# LCD_PCB_SCHEMETIC.net
KiCad netlist of a schematic drawn in Altium Designer
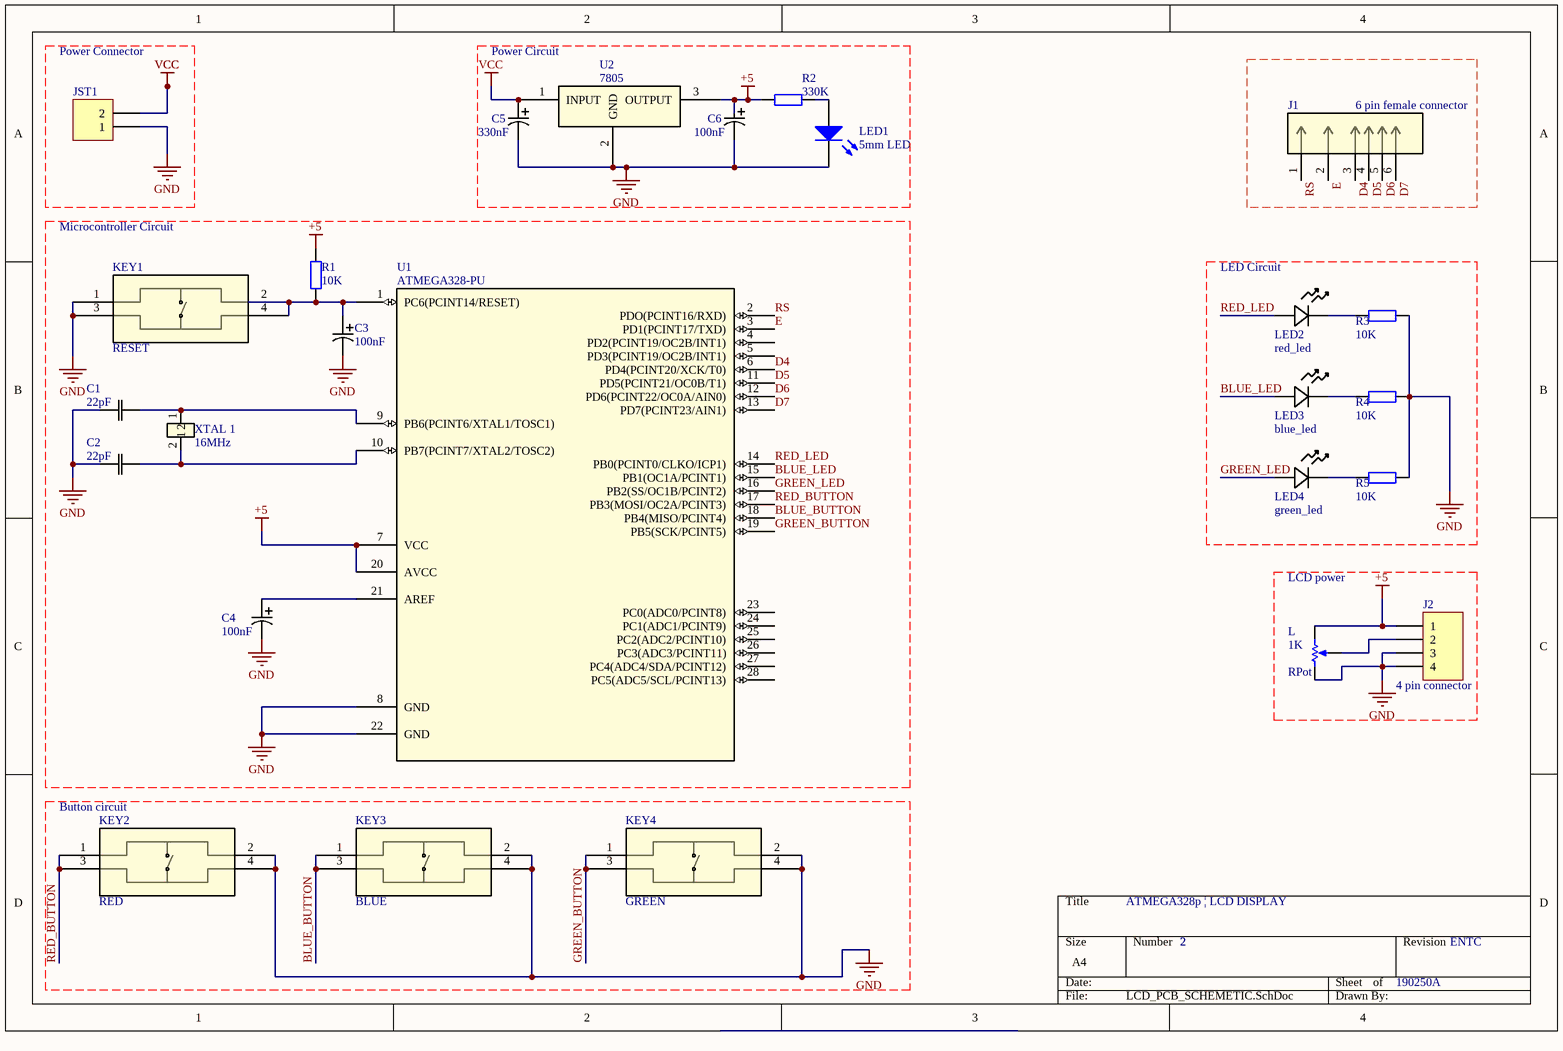
[diagram p0: LCD_PCB_SCHEMETIC.SchDoc]

(export (version "E")
  (design (tool "Eeschema 10.0.6"))
  (components
    (comp (ref "C1")
      (value "22pF")
      (footprint "CAP_K220J15C0GF53L2_VIS")
      (description "No Description Available")
      (fields
        (field (name "MANUFACTURER_PART_NUMBER") "K220J15C0GF53L2")
        (field (name "COPYRIGHT") "Copyright (C) 2018 Accelerated Designs. All rights reserved")
      )
      (libsource (lib "2021-05-23_06-09-59") (part "K220J15C0GF53L2"))
    )
    (comp (ref "C2")
      (value "22pF")
      (footprint "CAP_K220J15C0GF53L2_VIS")
      (description "No Description Available")
      (fields
        (field (name "MANUFACTURER_PART_NUMBER") "K220J15C0GF53L2")
        (field (name "COPYRIGHT") "Copyright (C) 2018 Accelerated Designs. All rights reserved")
      )
      (libsource (lib "2021-05-23_06-09-59") (part "K220J15C0GF53L2"))
    )
    (comp (ref "C3")
      (value "100nF")
      (footprint "PCAP_10x16_PAN")
      (description "No Description Available")
      (fields
        (field (name "MANUFACTURER_PART_NUMBER") "ECA2GM4R7")
        (field (name "COPYRIGHT") "Copyright (C) 2018 Accelerated Designs. All rights reserved")
      )
      (libsource (lib "2021-05-23_06-26-49") (part "ECA2GM4R7"))
    )
    (comp (ref "C4")
      (value "100nF")
      (footprint "PCAP_10x16_PAN")
      (description "No Description Available")
      (fields
        (field (name "MANUFACTURER_PART_NUMBER") "ECA2GM4R7")
        (field (name "COPYRIGHT") "Copyright (C) 2018 Accelerated Designs. All rights reserved")
      )
      (libsource (lib "2021-05-23_06-26-49") (part "ECA2GM4R7"))
    )
    (comp (ref "C5")
      (value "330nF")
      (footprint "PCAP_10x16_PAN")
      (description "No Description Available")
      (fields
        (field (name "MANUFACTURER_PART_NUMBER") "ECA2GM4R7")
        (field (name "COPYRIGHT") "Copyright (C) 2018 Accelerated Designs. All rights reserved")
      )
      (libsource (lib "2021-05-23_06-26-49") (part "ECA2GM4R7"))
    )
    (comp (ref "C6")
      (value "100nF")
      (footprint "PCAP_10x16_PAN")
      (description "No Description Available")
      (fields
        (field (name "MANUFACTURER_PART_NUMBER") "ECA2GM4R7")
        (field (name "COPYRIGHT") "Copyright (C) 2018 Accelerated Designs. All rights reserved")
      )
      (libsource (lib "2021-05-23_06-26-49") (part "ECA2GM4R7"))
    )
    (comp (ref "J1")
      (value "6 pin female connector")
      (footprint "CONN6_1744055-6")
      (description "3.96 EP HDR ASSY 6P VERT HT")
      (fields
        (field (name "MANUFACTURER_PART_NUMBER") "1744055-6")
        (field (name "COPYRIGHT") "Copyright (C) 2016 Accelerated Designs. All rights reserved")
      )
      (libsource (lib "2021-05-28_02-54-31") (part "1744055-6"))
    )
    (comp (ref "J2")
      (value "4 pin connector")
      (footprint "HDR1X4")
      (description "Header, 4-Pin")
      (fields (field (name "PUBLISHER") "Altium Limited"))
      (libsource (lib "Miscellaneous Connectors") (part "Header 4"))
    )
    (comp (ref "JST1")
      (value "~")
      (footprint "MHDR1X2")
      (description "Header, 2-Pin")
      (fields (field (name "PUBLISHER") "Altium Limited"))
      (libsource (lib "Miscellaneous Connectors") (part "MHDR1X2"))
    )
    (comp (ref "KEY1")
      (value "RESET")
      (footprint "TL1100F")
      (description "No Description Available")
      (fields
        (field (name "MANUFACTURER_PART_NUMBER") "TL1100FF160Q")
        (field (name "COPYRIGHT") "Copyright (C) 2018 Accelerated Designs. All rights reserved")
      )
      (libsource (lib "2021-05-24_16-22-31") (part "TL1100FF160Q"))
    )
    (comp (ref "KEY2")
      (value "RED")
      (footprint "TL1100F")
      (description "No Description Available")
      (fields
        (field (name "MANUFACTURER_PART_NUMBER") "TL1100FF160Q")
        (field (name "COPYRIGHT") "Copyright (C) 2018 Accelerated Designs. All rights reserved")
      )
      (libsource (lib "2021-05-24_16-22-31") (part "TL1100FF160Q"))
    )
    (comp (ref "KEY3")
      (value "BLUE")
      (footprint "TL1100F")
      (description "No Description Available")
      (fields
        (field (name "MANUFACTURER_PART_NUMBER") "TL1100FF160Q")
        (field (name "COPYRIGHT") "Copyright (C) 2018 Accelerated Designs. All rights reserved")
      )
      (libsource (lib "2021-05-24_16-22-31") (part "TL1100FF160Q"))
    )
    (comp (ref "KEY4")
      (value "GREEN")
      (footprint "TL1100F")
      (description "No Description Available")
      (fields
        (field (name "MANUFACTURER_PART_NUMBER") "TL1100FF160Q")
        (field (name "COPYRIGHT") "Copyright (C) 2018 Accelerated Designs. All rights reserved")
      )
      (libsource (lib "2021-05-24_16-22-31") (part "TL1100FF160Q"))
    )
    (comp (ref "L")
      (value "RPot")
      (footprint "VR5")
      (description "Potentiometer")
      (fields (field (name "ALTIUM_VALUE") "1K") (field (name "PUBLISHER") "Altium Limited"))
      (libsource (lib "Miscellaneous Devices") (part "RPot"))
    )
    (comp (ref "LED1")
      (value "5mm LED")
      (footprint "LED-0")
      (description "Typical INFRARED GaAs LED")
      (fields (field (name "PUBLISHER") "Altium Limited"))
      (libsource (lib "Miscellaneous Devices") (part "LED0"))
    )
    (comp (ref "LED2")
      (value "red_led")
      (footprint "LED_SSL-LX5093BID_LUM")
      (description "No Description Available")
      (fields
        (field (name "MANUFACTURER_PART_NUMBER") "SSL-LX5093BID")
        (field (name "COPYRIGHT") "Copyright (C) 2018 Accelerated Designs. All rights reserved")
      )
      (libsource (lib "2021-05-23_09-01-29") (part "SSL-LX5093BID"))
    )
    (comp (ref "LED3")
      (value "blue_led")
      (footprint "LED_SSL-LX5093BID_LUM")
      (description "No Description Available")
      (fields
        (field (name "MANUFACTURER_PART_NUMBER") "SSL-LX5093BID")
        (field (name "COPYRIGHT") "Copyright (C) 2018 Accelerated Designs. All rights reserved")
      )
      (libsource (lib "2021-05-23_09-01-29") (part "SSL-LX5093BID"))
    )
    (comp (ref "LED4")
      (value "green_led")
      (footprint "LED_SSL-LX5093BID_LUM")
      (description "No Description Available")
      (fields
        (field (name "MANUFACTURER_PART_NUMBER") "SSL-LX5093BID")
        (field (name "COPYRIGHT") "Copyright (C) 2018 Accelerated Designs. All rights reserved")
      )
      (libsource (lib "2021-05-23_09-01-29") (part "SSL-LX5093BID"))
    )
    (comp (ref "R1")
      (value "10K")
      (footprint "AXIAL-0.4")
      (description "Resistor")
      (fields (field (name "PUBLISHER") "Altium Limited"))
      (libsource (lib "") (part "Res2_1"))
    )
    (comp (ref "R2")
      (value "330K")
      (footprint "AXIAL-0.4")
      (description "Resistor")
      (fields (field (name "PUBLISHER") "Altium Limited"))
      (libsource (lib "") (part "Res2_2"))
    )
    (comp (ref "R3")
      (value "10K")
      (footprint "AXIAL-0.4")
      (description "Resistor")
      (fields (field (name "PUBLISHER") "Altium Limited"))
      (libsource (lib "Miscellaneous Devices") (part "Res2"))
    )
    (comp (ref "R4")
      (value "10K")
      (footprint "AXIAL-0.4")
      (description "Resistor")
      (fields (field (name "PUBLISHER") "Altium Limited"))
      (libsource (lib "Miscellaneous Devices") (part "Res2"))
    )
    (comp (ref "R5")
      (value "10K")
      (footprint "AXIAL-0.4")
      (description "Resistor")
      (fields (field (name "PUBLISHER") "Altium Limited"))
      (libsource (lib "Miscellaneous Devices") (part "Res2"))
    )
    (comp (ref "U1")
      (value "ATMEGA328-PU")
      (footprint "28P3_SPDIP28_SP_MCH")
      (description "No Description Available")
      (fields (field (name "COPYRIGHT") "Copyright (C) 2018 Accelerated Designs. All rights reserved"))
      (libsource (lib "2021-05-23_04-42-26") (part "ATMEGA328-PU_1"))
    )
    (comp (ref "U2")
      (value "7805")
      (footprint "TO-220_FAS")
      (description "No Description Available")
      (fields
        (field (name "MANUFACTURER_PART_NUMBER") "LM7805CT")
        (field (name "COPYRIGHT") "Copyright (C) 2018 Accelerated Designs. All rights reserved")
      )
      (libsource (lib "2021-05-23_07-25-23") (part "LM7805CT"))
    )
    (comp (ref "XTAL 1")
      (value "16MHz")
      (footprint "SMD_ABLS_11P4X4P7_ABR")
      (description "No Description Available")
      (fields
        (field (name "MANUFACTURER_PART_NUMBER") "ABLS-16.000MHZ-B4-T")
        (field (name "COPYRIGHT") "Copyright (C) 2018 Accelerated Designs. All rights reserved")
      )
      (libsource (lib "2021-05-23_05-42-48") (part "ABLS-16.000MHZ-B4-T"))
    )
  )
  (nets
    (net (code "1") (name "+5") (class "Default")
      (node (ref "C6") (pin "1") (pinfunction "1_1") (pintype "passive"))
      (node (ref "J2") (pin "1") (pinfunction "1_1") (pintype "passive"))
      (node (ref "L") (pin "2") (pinfunction "BOT_2") (pintype "passive"))
      (node (ref "R1") (pin "2") (pinfunction "2_2") (pintype "passive"))
      (node (ref "R2") (pin "1") (pinfunction "1_1") (pintype "passive"))
      (node (ref "U1") (pin "20") (pinfunction "AVCC_20") (pintype "power_in"))
      (node (ref "U1") (pin "7") (pinfunction "VCC_7") (pintype "power_in"))
      (node (ref "U2") (pin "3") (pinfunction "OUTPUT_3") (pintype "power_in"))
    )
    (net (code "2") (name "/BLUE_BUTTON") (class "Default")
      (node (ref "KEY3") (pin "1") (pinfunction "1_1") (pintype "passive"))
      (node (ref "KEY3") (pin "3") (pinfunction "3_3") (pintype "passive"))
      (node (ref "U1") (pin "18") (pinfunction "PB4(MISO/PCINT4)_18") (pintype "bidirectional"))
    )
    (net (code "3") (name "/BLUE_LED") (class "Default")
      (node (ref "LED3") (pin "2") (pinfunction "2_2") (pintype "passive"))
      (node (ref "U1") (pin "15") (pinfunction "PB1(OC1A/PCINT1)_15") (pintype "bidirectional"))
    )
    (net (code "4") (name "/D4") (class "Default")
      (node (ref "J1") (pin "3") (pinfunction "3_3") (pintype "passive"))
      (node (ref "U1") (pin "6") (pinfunction "PD4(PCINT20/XCK/T0)_6") (pintype "bidirectional"))
    )
    (net (code "5") (name "/D5") (class "Default")
      (node (ref "J1") (pin "4") (pinfunction "4_4") (pintype "passive"))
      (node (ref "U1") (pin "11") (pinfunction "PD5(PCINT21/OC0B/T1)_11") (pintype "bidirectional"))
    )
    (net (code "6") (name "/D6") (class "Default")
      (node (ref "J1") (pin "5") (pinfunction "5_5") (pintype "passive"))
      (node (ref "U1") (pin "12") (pinfunction "PD6(PCINT22/OC0A/AIN0)_12") (pintype "bidirectional"))
    )
    (net (code "7") (name "/D7") (class "Default")
      (node (ref "J1") (pin "6") (pinfunction "6_6") (pintype "passive"))
      (node (ref "U1") (pin "13") (pinfunction "PD7(PCINT23/AIN1)_13") (pintype "bidirectional"))
    )
    (net (code "8") (name "/E") (class "Default")
      (node (ref "J1") (pin "2") (pinfunction "2_2") (pintype "passive"))
      (node (ref "U1") (pin "3") (pinfunction "PD1(PCINT17/TXD)_3") (pintype "bidirectional"))
    )
    (net (code "9") (name "/GREEN_BUTTON") (class "Default")
      (node (ref "KEY4") (pin "1") (pinfunction "1_1") (pintype "passive"))
      (node (ref "KEY4") (pin "3") (pinfunction "3_3") (pintype "passive"))
      (node (ref "U1") (pin "19") (pinfunction "PB5(SCK/PCINT5)_19") (pintype "bidirectional"))
    )
    (net (code "10") (name "/GREEN_LED") (class "Default")
      (node (ref "LED4") (pin "2") (pinfunction "2_2") (pintype "passive"))
      (node (ref "U1") (pin "16") (pinfunction "PB2(SS/OC1B/PCINT2)_16") (pintype "bidirectional"))
    )
    (net (code "11") (name "/RED_BUTTON") (class "Default")
      (node (ref "KEY2") (pin "1") (pinfunction "1_1") (pintype "passive"))
      (node (ref "KEY2") (pin "3") (pinfunction "3_3") (pintype "passive"))
      (node (ref "U1") (pin "17") (pinfunction "PB3(MOSI/OC2A/PCINT3)_17") (pintype "bidirectional"))
    )
    (net (code "12") (name "/RED_LED") (class "Default")
      (node (ref "LED2") (pin "2") (pinfunction "2_2") (pintype "passive"))
      (node (ref "U1") (pin "14") (pinfunction "PB0(PCINT0/CLKO/ICP1)_14") (pintype "bidirectional"))
    )
    (net (code "13") (name "/RS") (class "Default")
      (node (ref "J1") (pin "1") (pinfunction "1_1") (pintype "passive"))
      (node (ref "U1") (pin "2") (pinfunction "PDO(PCINT16/RXD)_2") (pintype "bidirectional"))
    )
    (net (code "14") (name "GND") (class "Default")
      (node (ref "C1") (pin "2") (pinfunction "2_2") (pintype "passive"))
      (node (ref "C2") (pin "2") (pinfunction "2_2") (pintype "passive"))
      (node (ref "C3") (pin "2") (pinfunction "2_2") (pintype "passive"))
      (node (ref "C4") (pin "2") (pinfunction "2_2") (pintype "passive"))
      (node (ref "C5") (pin "2") (pinfunction "2_2") (pintype "passive"))
      (node (ref "C6") (pin "2") (pinfunction "2_2") (pintype "passive"))
      (node (ref "J2") (pin "3") (pinfunction "3_3") (pintype "passive"))
      (node (ref "J2") (pin "4") (pinfunction "4_4") (pintype "passive"))
      (node (ref "JST1") (pin "1") (pinfunction "1_1") (pintype "passive"))
      (node (ref "KEY1") (pin "1") (pinfunction "1_1") (pintype "passive"))
      (node (ref "KEY1") (pin "3") (pinfunction "3_3") (pintype "passive"))
      (node (ref "KEY2") (pin "2") (pinfunction "2_2") (pintype "passive"))
      (node (ref "KEY2") (pin "4") (pinfunction "4_4") (pintype "passive"))
      (node (ref "KEY3") (pin "2") (pinfunction "2_2") (pintype "passive"))
      (node (ref "KEY3") (pin "4") (pinfunction "4_4") (pintype "passive"))
      (node (ref "KEY4") (pin "2") (pinfunction "2_2") (pintype "passive"))
      (node (ref "KEY4") (pin "4") (pinfunction "4_4") (pintype "passive"))
      (node (ref "L") (pin "1") (pinfunction "TOP_1") (pintype "passive"))
      (node (ref "LED1") (pin "2") (pinfunction "K_2") (pintype "passive"))
      (node (ref "R3") (pin "1") (pinfunction "1_1") (pintype "passive"))
      (node (ref "R4") (pin "1") (pinfunction "1_1") (pintype "passive"))
      (node (ref "R5") (pin "1") (pinfunction "1_1") (pintype "passive"))
      (node (ref "U1") (pin "22") (pinfunction "GND_22") (pintype "passive"))
      (node (ref "U1") (pin "8") (pinfunction "GND_8") (pintype "passive"))
      (node (ref "U2") (pin "2") (pinfunction "GND_2") (pintype "power_in"))
    )
    (net (code "15") (name "Net-(L-TAP)") (class "Default")
      (node (ref "J2") (pin "2") (pinfunction "2_2") (pintype "passive"))
      (node (ref "L") (pin "3") (pinfunction "TAP_3") (pintype "passive"))
    )
    (net (code "16") (name "Net-(LED1-A)") (class "Default")
      (node (ref "LED1") (pin "1") (pinfunction "A_1") (pintype "passive"))
      (node (ref "R2") (pin "2") (pinfunction "2_2") (pintype "passive"))
    )
    (net (code "17") (name "Net-(LED2-Pad1)") (class "Default")
      (node (ref "LED2") (pin "1") (pinfunction "1_1") (pintype "passive"))
      (node (ref "R3") (pin "2") (pinfunction "2_2") (pintype "passive"))
    )
    (net (code "18") (name "Net-(LED3-Pad1)") (class "Default")
      (node (ref "LED3") (pin "1") (pinfunction "1_1") (pintype "passive"))
      (node (ref "R4") (pin "2") (pinfunction "2_2") (pintype "passive"))
    )
    (net (code "19") (name "Net-(LED4-Pad1)") (class "Default")
      (node (ref "LED4") (pin "1") (pinfunction "1_1") (pintype "passive"))
      (node (ref "R5") (pin "2") (pinfunction "2_2") (pintype "passive"))
    )
    (net (code "20") (name "Net-(U1-AREF)") (class "Default")
      (node (ref "C4") (pin "1") (pinfunction "1_1") (pintype "passive"))
      (node (ref "U1") (pin "21") (pinfunction "AREF_21") (pintype "passive"))
    )
    (net (code "21") (name "Net-(U1-PB6(PCINT6{slash}XTAL1{slash}TOSC1))") (class "Default")
      (node (ref "C1") (pin "1") (pinfunction "1_1") (pintype "passive"))
      (node (ref "U1") (pin "9") (pinfunction "PB6(PCINT6/XTAL1/TOSC1)_9") (pintype "bidirectional"))
      (node (ref "XTAL 1") (pin "1") (pinfunction "1_1") (pintype "passive"))
    )
    (net (code "22") (name "Net-(U1-PB7(PCINT7{slash}XTAL2{slash}TOSC2))") (class "Default")
      (node (ref "C2") (pin "1") (pinfunction "1_1") (pintype "passive"))
      (node (ref "U1") (pin "10") (pinfunction "PB7(PCINT7/XTAL2/TOSC2)_10") (pintype "bidirectional"))
      (node (ref "XTAL 1") (pin "2") (pinfunction "2_2") (pintype "passive"))
    )
    (net (code "23") (name "Net-(U1-PC6(PCINT14{slash}RESET))") (class "Default")
      (node (ref "C3") (pin "1") (pinfunction "1_1") (pintype "passive"))
      (node (ref "KEY1") (pin "2") (pinfunction "2_2") (pintype "passive"))
      (node (ref "KEY1") (pin "4") (pinfunction "4_4") (pintype "passive"))
      (node (ref "R1") (pin "1") (pinfunction "1_1") (pintype "passive"))
      (node (ref "U1") (pin "1") (pinfunction "PC6(PCINT14/RESET)_1") (pintype "bidirectional"))
    )
    (net (code "24") (name "VCC") (class "Default")
      (node (ref "C5") (pin "1") (pinfunction "1_1") (pintype "passive"))
      (node (ref "JST1") (pin "2") (pinfunction "2_2") (pintype "passive"))
      (node (ref "U2") (pin "1") (pinfunction "INPUT_1") (pintype "power_in"))
    )
    (net (code "25") (name "unconnected-(U1-PC0(ADC0{slash}PCINT8)-Pad23)") (class "Default")
      (node (ref "U1") (pin "23") (pinfunction "PC0(ADC0/PCINT8)_23") (pintype "bidirectional"))
    )
    (net (code "26") (name "unconnected-(U1-PC1(ADC1{slash}PCINT9)-Pad24)") (class "Default")
      (node (ref "U1") (pin "24") (pinfunction "PC1(ADC1/PCINT9)_24") (pintype "bidirectional"))
    )
    (net (code "27") (name "unconnected-(U1-PC2(ADC2{slash}PCINT10)-Pad25)") (class "Default")
      (node (ref "U1") (pin "25") (pinfunction "PC2(ADC2/PCINT10)_25") (pintype "bidirectional"))
    )
    (net (code "28") (name "unconnected-(U1-PC3(ADC3{slash}PCINT11)-Pad26)") (class "Default")
      (node (ref "U1") (pin "26") (pinfunction "PC3(ADC3/PCINT11)_26") (pintype "bidirectional"))
    )
    (net (code "29") (name "unconnected-(U1-PC4(ADC4{slash}SDA{slash}PCINT12)-Pad27)") (class "Default")
      (node (ref "U1") (pin "27") (pinfunction "PC4(ADC4/SDA/PCINT12)_27") (pintype "bidirectional"))
    )
    (net (code "30") (name "unconnected-(U1-PC5(ADC5{slash}SCL{slash}PCINT13)-Pad28)") (class "Default")
      (node (ref "U1") (pin "28") (pinfunction "PC5(ADC5/SCL/PCINT13)_28") (pintype "bidirectional"))
    )
    (net (code "31") (name "unconnected-(U1-PD2(PCINT19{slash}OC2B{slash}INT1)-Pad4)") (class "Default")
      (node (ref "U1") (pin "4") (pinfunction "PD2(PCINT19/OC2B/INT1)_4") (pintype "bidirectional"))
    )
    (net (code "32") (name "unconnected-(U1-PD3(PCINT19{slash}OC2B{slash}INT1)-Pad5)") (class "Default")
      (node (ref "U1") (pin "5") (pinfunction "PD3(PCINT19/OC2B/INT1)_5") (pintype "bidirectional"))
    )
  )
)
